# ActiveElectrod.net
KiCad netlist of a schematic drawn in Altium Designer
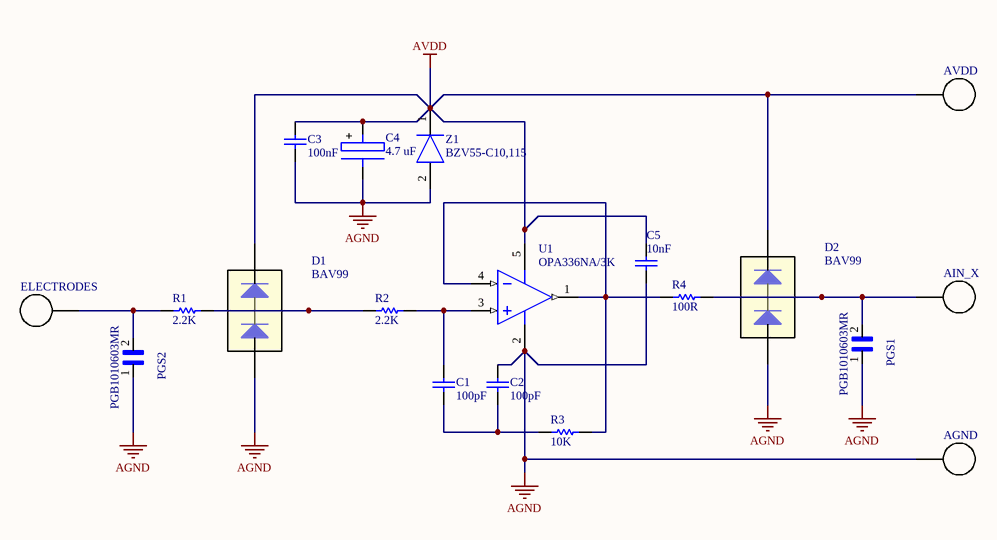
[diagram p0: ActiveElectrod.SchDoc]

(export (version "E")
  (design (tool "Eeschema 10.0.6"))
  (components
    (comp (ref "AGND")
      (value "Test Point 1")
      (footprint "Test Point")
      (description "Header, 1-Pin")
      (fields (field (name "PUBLISHER") "Sergeev"))
      (libsource (lib "Sergeev_27.03.2014") (part "Test Point 1"))
    )
    (comp (ref "AIN_X")
      (value "Test Point 1")
      (footprint "Test Point")
      (description "Header, 1-Pin")
      (fields (field (name "PUBLISHER") "Sergeev"))
      (libsource (lib "Sergeev_27.03.2014") (part "Test Point 1"))
    )
    (comp (ref "AVDD")
      (value "Test Point 1")
      (footprint "Test Point")
      (description "Header, 1-Pin")
      (fields (field (name "PUBLISHER") "Sergeev"))
      (libsource (lib "Sergeev_27.03.2014") (part "Test Point 1"))
    )
    (comp (ref "C1")
      (value "100pF")
      (footprint "J1-0603")
      (description "Capacitor (Semiconductor SIM Model)")
      (fields (field (name "Comment") "Cap Semi") (field (name "PUBLISHER") "Altium Limited"))
      (libsource (lib "Miscellaneous Devices") (part "Cap Semi"))
    )
    (comp (ref "C2")
      (value "100pF")
      (footprint "J1-0603")
      (description "Capacitor (Semiconductor SIM Model)")
      (fields (field (name "Comment") "Cap Semi") (field (name "PUBLISHER") "Altium Limited"))
      (libsource (lib "Miscellaneous Devices") (part "Cap Semi"))
    )
    (comp (ref "C3")
      (value "100nF")
      (footprint "J1-0603")
      (description "Capacitor (Semiconductor SIM Model)")
      (fields (field (name "Comment") "Cap Semi") (field (name "PUBLISHER") "Altium Limited"))
      (libsource (lib "Miscellaneous Devices") (part "Cap Semi"))
    )
    (comp (ref "C4")
      (value "4.7 uF")
      (footprint "3528 - Type B")
      (description "Capacitor (Model Sergeev)")
      (fields (field (name "Comment") "Cap polar_Vishay Type B") (field (name "PUBLISHER") "Sergeev"))
      (libsource (lib "Sergeev_27.03.2014") (part "Cap polar_Vishay Type B"))
    )
    (comp (ref "C5")
      (value "10nF")
      (footprint "J1-0603")
      (description "Capacitor (Semiconductor SIM Model)")
      (fields (field (name "Comment") "Cap Semi") (field (name "PUBLISHER") "Altium Limited"))
      (libsource (lib "Miscellaneous Devices") (part "Cap Semi"))
    )
    (comp (ref "D1")
      (value "BAV99")
      (footprint "SOT-23")
      (description "Диодная сборка, 2 диода, катод/анод, 100 V, 125/215 mA, Iобр.=0.5 uA, 4 ns")
      (fields (field (name "РАЗРАБОТАЛ") "Сергеев"))
      (libsource (lib "Sergeev_27.03.2014") (part "BAV99"))
    )
    (comp (ref "D2")
      (value "BAV99")
      (footprint "SOT-23")
      (description "Диодная сборка, 2 диода, катод/анод, 100 V, 125/215 mA, Iобр.=0.5 uA, 4 ns")
      (fields (field (name "РАЗРАБОТАЛ") "Сергеев"))
      (libsource (lib "Sergeev_27.03.2014") (part "BAV99"))
    )
    (comp (ref "ELECTRODES")
      (value "Test Point 1")
      (footprint "Test Point")
      (description "Header, 1-Pin")
      (fields (field (name "PUBLISHER") "Sergeev"))
      (libsource (lib "Sergeev_27.03.2014") (part "Test Point 1"))
    )
    (comp (ref "PGS1")
      (value "PGB1010603MR")
      (footprint "*ESD_PGB1010603MR")
      (description "PGB1 Series 15 V 63 Bi-Directional Surface Mount PulseGuardВ® ESD Suppressor")
      (fields (field (name "MF") "Littelfuse Inc."))
      (libsource (lib "PGB1010603MR") (part "PGB1010603MR"))
    )
    (comp (ref "PGS2")
      (value "PGB1010603MR")
      (footprint "*ESD_PGB1010603MR")
      (description "PGB1 Series 15 V 63 Bi-Directional Surface Mount PulseGuardВ® ESD Suppressor")
      (fields (field (name "MF") "Littelfuse Inc."))
      (libsource (lib "PGB1010603MR") (part "PGB1010603MR"))
    )
    (comp (ref "R1")
      (value "2.2K")
      (footprint "J1-0603")
      (description "Resistor")
      (fields (field (name "Comment") "Res1") (field (name "PUBLISHER") "Altium Limited"))
      (libsource (lib "Miscellaneous Devices") (part "Res1"))
    )
    (comp (ref "R2")
      (value "2.2K")
      (footprint "J1-0603")
      (description "Resistor")
      (fields (field (name "Comment") "Res1") (field (name "PUBLISHER") "Altium Limited"))
      (libsource (lib "Miscellaneous Devices") (part "Res1"))
    )
    (comp (ref "R3")
      (value "10K")
      (footprint "J1-0603")
      (description "Resistor")
      (fields (field (name "Comment") "Res1") (field (name "PUBLISHER") "Altium Limited"))
      (libsource (lib "Miscellaneous Devices") (part "Res1"))
    )
    (comp (ref "R4")
      (value "100R")
      (footprint "J1-0603")
      (description "Resistor")
      (fields (field (name "Comment") "Res1") (field (name "PUBLISHER") "Altium Limited"))
      (libsource (lib "Miscellaneous Devices") (part "Res1"))
    )
    (comp (ref "U1")
      (value "OPA336NA/3K")
      (footprint "TI-DBV5_N")
      (fields (field (name "MANUFACTURER") "Texas Instruments"))
      (libsource (lib "TI Amplifiers and Linear Operational Amplifier Precision Amplifier Part One") (part "OPA336NA/3K"))
    )
    (comp (ref "Z1")
      (value "BZV55-C10,115")
      (footprint "BZV55:BZV55-C10")
      (description "Diode")
      (fields
        (field (name "MOUSER PART NUMBER") "771-BZV55-C10-T/R")
        (field (name "RS PART NUMBER") "0788508")
      )
      (libsource (lib "BZV55") (part "BZV55-C10,115"))
    )
  )
  (nets
    (net (code "1") (name "AGND") (class "Default")
      (node (ref "AGND") (pin "1") (pinfunction "1_1") (pintype "passive"))
      (node (ref "C2") (pin "1") (pinfunction "1_1") (pintype "passive"))
      (node (ref "C3") (pin "1") (pinfunction "1_1") (pintype "passive"))
      (node (ref "C4") (pin "2") (pinfunction "2_2") (pintype "passive"))
      (node (ref "C5") (pin "2") (pinfunction "2_2") (pintype "passive"))
      (node (ref "D1") (pin "1") (pinfunction "A_1") (pintype "passive"))
      (node (ref "D2") (pin "1") (pinfunction "A_1") (pintype "passive"))
      (node (ref "PGS1") (pin "1") (pinfunction "1_1") (pintype "passive"))
      (node (ref "PGS2") (pin "1") (pinfunction "1_1") (pintype "passive"))
      (node (ref "U1") (pin "2") (pinfunction "V-_2") (pintype "power_in"))
      (node (ref "Z1") (pin "2") (pinfunction "2_2") (pintype "passive"))
    )
    (net (code "2") (name "AVDD") (class "Default")
      (node (ref "AVDD") (pin "1") (pinfunction "1_1") (pintype "passive"))
      (node (ref "C3") (pin "2") (pinfunction "2_2") (pintype "passive"))
      (node (ref "C4") (pin "1") (pinfunction "1_1") (pintype "passive"))
      (node (ref "C5") (pin "1") (pinfunction "1_1") (pintype "passive"))
      (node (ref "D1") (pin "2") (pinfunction "K_2") (pintype "passive"))
      (node (ref "D2") (pin "2") (pinfunction "K_2") (pintype "passive"))
      (node (ref "U1") (pin "5") (pinfunction "V+_5") (pintype "power_in"))
      (node (ref "Z1") (pin "1") (pinfunction "1_1") (pintype "passive"))
    )
    (net (code "3") (name "Net-(AIN_X-Pad1)") (class "Default")
      (node (ref "AIN_X") (pin "1") (pinfunction "1_1") (pintype "passive"))
      (node (ref "D2") (pin "3") (pinfunction "3_3") (pintype "passive"))
      (node (ref "PGS1") (pin "2") (pinfunction "2_2") (pintype "passive"))
      (node (ref "R4") (pin "1") (pinfunction "1_1") (pintype "passive"))
    )
    (net (code "4") (name "Net-(C1-Pad2)") (class "Default")
      (node (ref "C1") (pin "2") (pinfunction "2_2") (pintype "passive"))
      (node (ref "C2") (pin "2") (pinfunction "2_2") (pintype "passive"))
      (node (ref "R3") (pin "2") (pinfunction "2_2") (pintype "passive"))
    )
    (net (code "5") (name "Net-(D1-Pad3)") (class "Default")
      (node (ref "D1") (pin "3") (pinfunction "3_3") (pintype "passive"))
      (node (ref "R1") (pin "1") (pinfunction "1_1") (pintype "passive"))
      (node (ref "R2") (pin "2") (pinfunction "2_2") (pintype "passive"))
    )
    (net (code "6") (name "Net-(ELECTRODES-Pad1)") (class "Default")
      (node (ref "ELECTRODES") (pin "1") (pinfunction "1_1") (pintype "passive"))
      (node (ref "PGS2") (pin "2") (pinfunction "2_2") (pintype "passive"))
      (node (ref "R1") (pin "2") (pinfunction "2_2") (pintype "passive"))
    )
    (net (code "7") (name "Net-(U1-IN+)") (class "Default")
      (node (ref "C1") (pin "1") (pinfunction "1_1") (pintype "passive"))
      (node (ref "R2") (pin "1") (pinfunction "1_1") (pintype "passive"))
      (node (ref "U1") (pin "3") (pinfunction "IN+_3") (pintype "input"))
    )
    (net (code "8") (name "Net-(U1-IN-)") (class "Default")
      (node (ref "R3") (pin "1") (pinfunction "1_1") (pintype "passive"))
      (node (ref "R4") (pin "2") (pinfunction "2_2") (pintype "passive"))
      (node (ref "U1") (pin "1") (pinfunction "OUT_1") (pintype "output"))
      (node (ref "U1") (pin "4") (pinfunction "IN-_4") (pintype "input"))
    )
  )
)
